# DRV8840_driver.net
KiCad netlist of a schematic drawn in Altium Designer
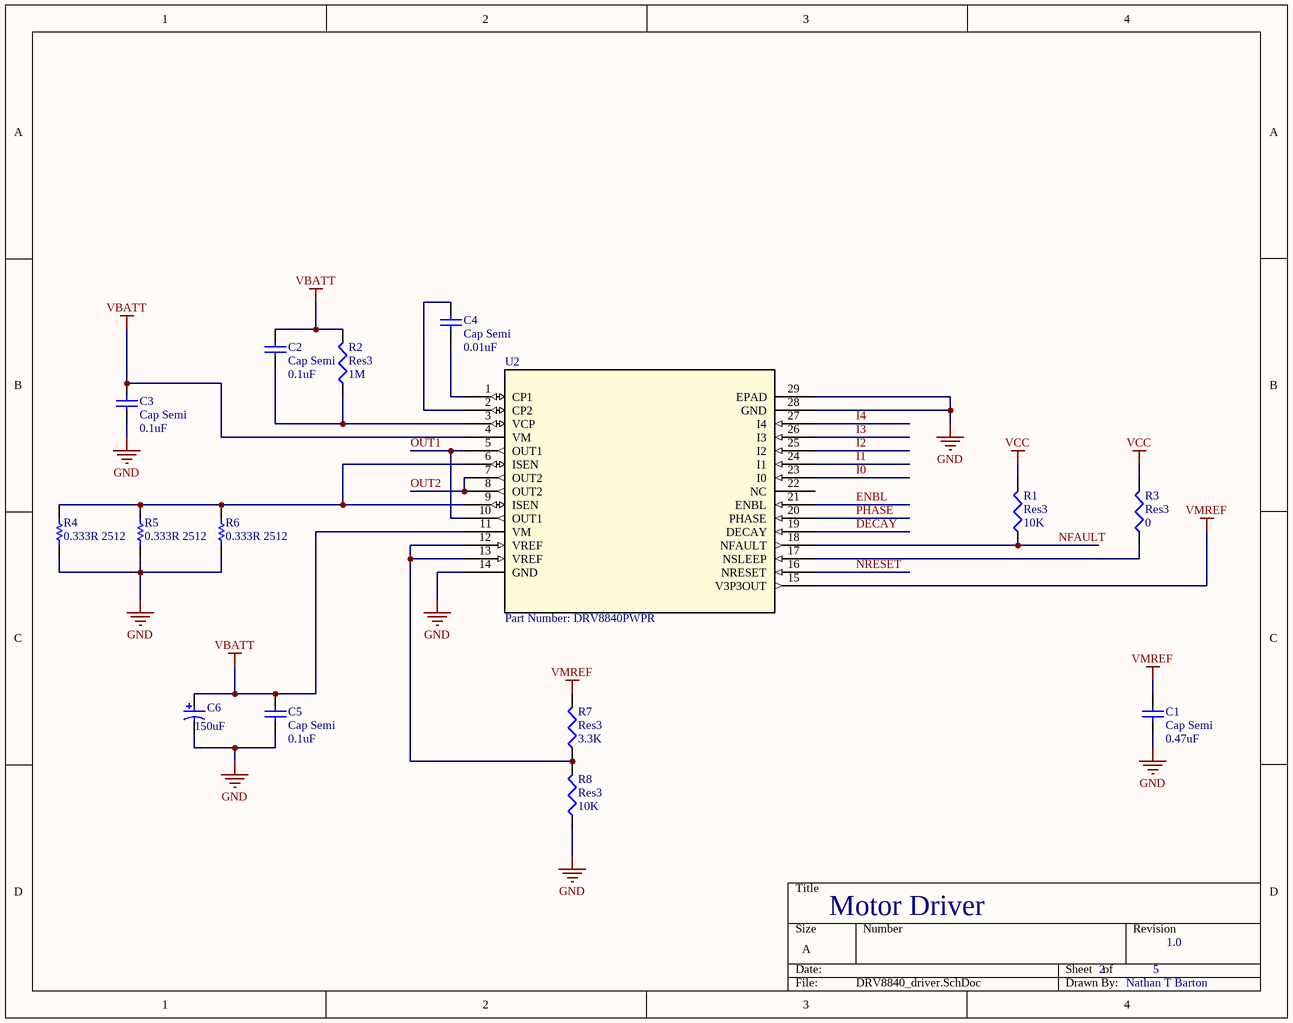
[diagram p0: DRV8840_driver.SchDoc]

(export (version "E")
  (design (tool "Eeschema 10.0.6"))
  (components
    (comp (ref "C1")
      (value "Cap Semi")
      (footprint "C1206")
      (description "Capacitor (Semiconductor SIM Model)")
      (fields (field (name "ALTIUM_VALUE") "0.47uF") (field (name "PUBLISHER") "Altium Limited"))
      (libsource (lib "Miscellaneous Devices") (part "Cap Semi"))
    )
    (comp (ref "C2")
      (value "Cap Semi")
      (footprint "C1206")
      (description "Capacitor (Semiconductor SIM Model)")
      (fields (field (name "ALTIUM_VALUE") "0.1uF") (field (name "PUBLISHER") "Altium Limited"))
      (libsource (lib "Miscellaneous Devices") (part "Cap Semi"))
    )
    (comp (ref "C3")
      (value "Cap Semi")
      (footprint "C1206")
      (description "Capacitor (Semiconductor SIM Model)")
      (fields (field (name "ALTIUM_VALUE") "0.1uF") (field (name "PUBLISHER") "Altium Limited"))
      (libsource (lib "Miscellaneous Devices") (part "Cap Semi"))
    )
    (comp (ref "C4")
      (value "Cap Semi")
      (footprint "C1206")
      (description "Capacitor (Semiconductor SIM Model)")
      (fields (field (name "ALTIUM_VALUE") "0.01uF") (field (name "PUBLISHER") "Altium Limited"))
      (libsource (lib "Miscellaneous Devices") (part "Cap Semi"))
    )
    (comp (ref "C5")
      (value "Cap Semi")
      (footprint "C1206")
      (description "Capacitor (Semiconductor SIM Model)")
      (fields (field (name "ALTIUM_VALUE") "0.1uF") (field (name "PUBLISHER") "Altium Limited"))
      (libsource (lib "Miscellaneous Devices") (part "Cap Semi"))
    )
    (comp (ref "C6")
      (value "150uF")
      (footprint "NIC-CAPA2-10X10_V")
      (fields (field (name "MANUFACTURER") "Nichicon") (field (name "PARTNUMBER") "UUD1H151MNL1GS"))
      (libsource (lib "spoolbot_library") (part "CMP-0687-00003-1"))
    )
    (comp (ref "R1")
      (value "Res3")
      (footprint "J1-0603")
      (description "Resistor")
      (fields (field (name "ALTIUM_VALUE") "10K") (field (name "PUBLISHER") "Altium Limited"))
      (libsource (lib "Miscellaneous Devices") (part "Res3"))
    )
    (comp (ref "R2")
      (value "Res3")
      (footprint "J1-0603")
      (description "Resistor")
      (fields (field (name "ALTIUM_VALUE") "1M") (field (name "PUBLISHER") "Altium Limited"))
      (libsource (lib "Miscellaneous Devices") (part "Res3"))
    )
    (comp (ref "R3")
      (value "Res3")
      (footprint "J1-0603")
      (description "Resistor")
      (fields (field (name "ALTIUM_VALUE") "0") (field (name "PUBLISHER") "Altium Limited"))
      (libsource (lib "Miscellaneous Devices") (part "Res3"))
    )
    (comp (ref "R4")
      (value "0.333R 2512")
      (footprint "RESC2512(6432)_M")
      (description "1R 1W 1% 2512 (6432 Metric)  SMD")
      (fields (field (name "TOLERANCE") "1 %") (field (name "POWER") "1 W"))
      (libsource (lib "Altium Content Vault") (part "RES"))
    )
    (comp (ref "R5")
      (value "0.333R 2512")
      (footprint "RESC2512(6432)_M")
      (description "1R 1W 1% 2512 (6432 Metric)  SMD")
      (fields (field (name "TOLERANCE") "1 %") (field (name "POWER") "1 W"))
      (libsource (lib "Altium Content Vault") (part "RES"))
    )
    (comp (ref "R6")
      (value "0.333R 2512")
      (footprint "RESC2512(6432)_M")
      (description "1R 1W 1% 2512 (6432 Metric)  SMD")
      (fields (field (name "TOLERANCE") "1 %") (field (name "POWER") "1 W"))
      (libsource (lib "Altium Content Vault") (part "RES"))
    )
    (comp (ref "R7")
      (value "Res3")
      (footprint "J1-0603")
      (description "Resistor")
      (fields (field (name "ALTIUM_VALUE") "3.3K") (field (name "PUBLISHER") "Altium Limited"))
      (libsource (lib "Miscellaneous Devices") (part "Res3"))
    )
    (comp (ref "R8")
      (value "Res3")
      (footprint "J1-0603")
      (description "Resistor")
      (fields (field (name "ALTIUM_VALUE") "10K") (field (name "PUBLISHER") "Altium Limited"))
      (libsource (lib "Miscellaneous Devices") (part "Res3"))
    )
    (comp (ref "U2")
      (value "Part Number: DRV8840PWPR")
      (footprint "PWP28_5P18X3P1")
      (description "No Description Available")
      (fields
        (field (name "MANUFACTURER") "Texas Instruments")
        (field (name "MANUFACTURER_PART_NUMBER") "DRV8840PWPR")
        (field (name "COPYRIGHT") "Copyright (C) 2018 Accelerated Designs. All rights reserved")
      )
      (libsource (lib "spoolbot_library") (part "DRV8840PWPR"))
    )
  )
  (nets
    (net (code "1") (name "/DECAY") (class "Default")
      (node (ref "U2") (pin "19") (pinfunction "DECAY_19") (pintype "input"))
    )
    (net (code "2") (name "/ENBL") (class "Default")
      (node (ref "U2") (pin "21") (pinfunction "ENBL_21") (pintype "input"))
    )
    (net (code "3") (name "/I0") (class "Default")
      (node (ref "U2") (pin "23") (pinfunction "I0_23") (pintype "input"))
    )
    (net (code "4") (name "/I1") (class "Default")
      (node (ref "U2") (pin "24") (pinfunction "I1_24") (pintype "input"))
    )
    (net (code "5") (name "/I2") (class "Default")
      (node (ref "U2") (pin "25") (pinfunction "I2_25") (pintype "input"))
    )
    (net (code "6") (name "/I3") (class "Default")
      (node (ref "U2") (pin "26") (pinfunction "I3_26") (pintype "input"))
    )
    (net (code "7") (name "/I4") (class "Default")
      (node (ref "U2") (pin "27") (pinfunction "I4_27") (pintype "input"))
    )
    (net (code "8") (name "/NFAULT") (class "Default")
      (node (ref "R1") (pin "1") (pinfunction "1_1") (pintype "passive"))
      (node (ref "U2") (pin "18") (pinfunction "NFAULT_18") (pintype "output"))
    )
    (net (code "9") (name "/NRESET") (class "Default")
      (node (ref "U2") (pin "16") (pinfunction "NRESET_16") (pintype "input"))
    )
    (net (code "10") (name "/OUT1") (class "Default")
      (node (ref "U2") (pin "10") (pinfunction "OUT1_10") (pintype "output"))
      (node (ref "U2") (pin "5") (pinfunction "OUT1_5") (pintype "output"))
    )
    (net (code "11") (name "/OUT2") (class "Default")
      (node (ref "U2") (pin "7") (pinfunction "OUT2_7") (pintype "output"))
      (node (ref "U2") (pin "8") (pinfunction "OUT2_8") (pintype "output"))
    )
    (net (code "12") (name "/PHASE") (class "Default")
      (node (ref "U2") (pin "20") (pinfunction "PHASE_20") (pintype "input"))
    )
    (net (code "13") (name "GND") (class "Default")
      (node (ref "C1") (pin "1") (pinfunction "1_1") (pintype "passive"))
      (node (ref "C3") (pin "1") (pinfunction "1_1") (pintype "passive"))
      (node (ref "C5") (pin "1") (pinfunction "1_1") (pintype "passive"))
      (node (ref "C6") (pin "2") (pinfunction "2_2") (pintype "passive"))
      (node (ref "R4") (pin "1") (pinfunction "1_1") (pintype "passive"))
      (node (ref "R5") (pin "1") (pinfunction "1_1") (pintype "passive"))
      (node (ref "R6") (pin "1") (pinfunction "1_1") (pintype "passive"))
      (node (ref "R8") (pin "1") (pinfunction "1_1") (pintype "passive"))
      (node (ref "U2") (pin "14") (pinfunction "GND_14") (pintype "power_in"))
      (node (ref "U2") (pin "28") (pinfunction "GND_28") (pintype "power_in"))
      (node (ref "U2") (pin "29") (pinfunction "EPAD_29") (pintype "passive"))
    )
    (net (code "14") (name "Net-(R4-Pad2)") (class "Default")
      (node (ref "R4") (pin "2") (pinfunction "2_2") (pintype "passive"))
      (node (ref "R5") (pin "2") (pinfunction "2_2") (pintype "passive"))
      (node (ref "R6") (pin "2") (pinfunction "2_2") (pintype "passive"))
      (node (ref "U2") (pin "6") (pinfunction "ISEN_6") (pintype "bidirectional"))
      (node (ref "U2") (pin "9") (pinfunction "ISEN_9") (pintype "bidirectional"))
    )
    (net (code "15") (name "Net-(R7-Pad1)") (class "Default")
      (node (ref "R7") (pin "1") (pinfunction "1_1") (pintype "passive"))
      (node (ref "R8") (pin "2") (pinfunction "2_2") (pintype "passive"))
      (node (ref "U2") (pin "12") (pinfunction "VREF_12") (pintype "input"))
      (node (ref "U2") (pin "13") (pinfunction "VREF_13") (pintype "input"))
    )
    (net (code "16") (name "Net-(U2-CP1)") (class "Default")
      (node (ref "C4") (pin "1") (pinfunction "1_1") (pintype "passive"))
      (node (ref "U2") (pin "1") (pinfunction "CP1_1") (pintype "bidirectional"))
    )
    (net (code "17") (name "Net-(U2-CP2)") (class "Default")
      (node (ref "C4") (pin "2") (pinfunction "2_2") (pintype "passive"))
      (node (ref "U2") (pin "2") (pinfunction "CP2_2") (pintype "bidirectional"))
    )
    (net (code "18") (name "Net-(U2-NSLEEP)") (class "Default")
      (node (ref "R3") (pin "1") (pinfunction "1_1") (pintype "passive"))
      (node (ref "U2") (pin "17") (pinfunction "NSLEEP_17") (pintype "input"))
    )
    (net (code "19") (name "Net-(U2-VCP)") (class "Default")
      (node (ref "C2") (pin "1") (pinfunction "1_1") (pintype "passive"))
      (node (ref "R2") (pin "1") (pinfunction "1_1") (pintype "passive"))
      (node (ref "U2") (pin "3") (pinfunction "VCP_3") (pintype "bidirectional"))
    )
    (net (code "20") (name "VBATT") (class "Default")
      (node (ref "C2") (pin "2") (pinfunction "2_2") (pintype "passive"))
      (node (ref "C3") (pin "2") (pinfunction "2_2") (pintype "passive"))
      (node (ref "C5") (pin "2") (pinfunction "2_2") (pintype "passive"))
      (node (ref "C6") (pin "1") (pinfunction "1_1") (pintype "passive"))
      (node (ref "R2") (pin "2") (pinfunction "2_2") (pintype "passive"))
      (node (ref "U2") (pin "11") (pinfunction "VM_11") (pintype "power_in"))
      (node (ref "U2") (pin "4") (pinfunction "VM_4") (pintype "power_in"))
    )
    (net (code "21") (name "VCC") (class "Default")
      (node (ref "R1") (pin "2") (pinfunction "2_2") (pintype "passive"))
      (node (ref "R3") (pin "2") (pinfunction "2_2") (pintype "passive"))
    )
    (net (code "22") (name "VMREF") (class "Default")
      (node (ref "C1") (pin "2") (pinfunction "2_2") (pintype "passive"))
      (node (ref "R7") (pin "2") (pinfunction "2_2") (pintype "passive"))
      (node (ref "U2") (pin "15") (pinfunction "V3P3OUT_15") (pintype "output"))
    )
    (net (code "23") (name "unconnected-(U2-NC-Pad22)") (class "Default")
      (node (ref "U2") (pin "22") (pinfunction "NC_22") (pintype "passive"))
    )
  )
)
